# ExpressionPedalAdapter.net
KiCad netlist of a schematic drawn in EAGLE
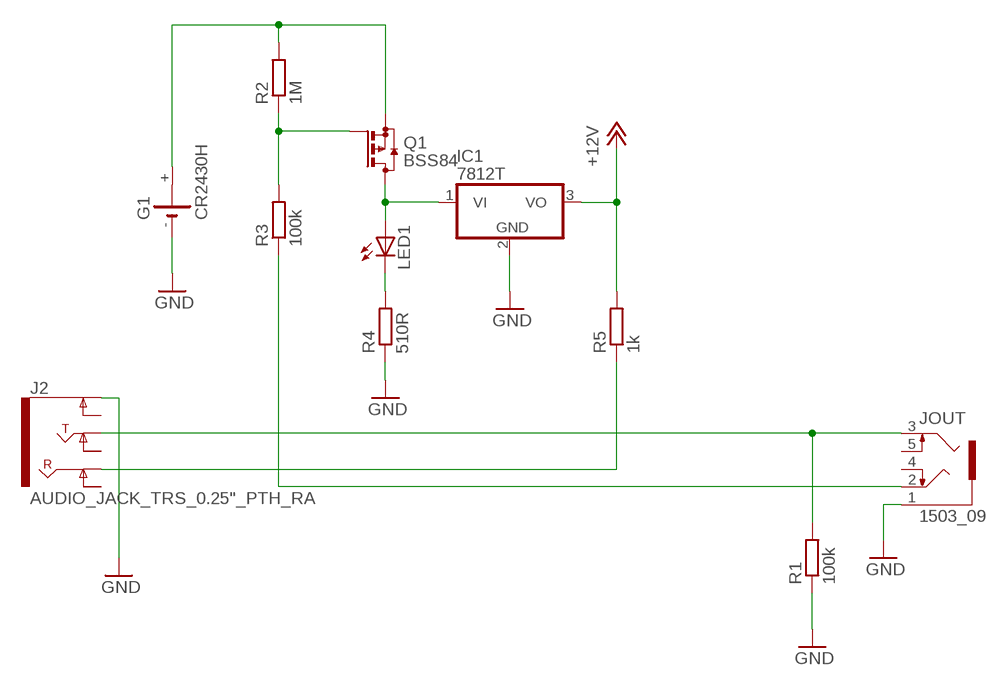
[diagram p0: schematic, sheet 1]

(export (version "E")
  (design (tool "Eeschema 10.0.6"))
  (components
    (comp (ref "G1")
      (value "CR2430H")
      (footprint "eagle-import:CR2430H")
      (libsource (lib "eagle-import") (part "CR2430H"))
    )
    (comp (ref "IC1")
      (value "7812T")
      (footprint "eagle-import:TO220H")
      (libsource (lib "eagle-import") (part "78T12"))
    )
    (comp (ref "J2")
      (value "AUDIO_JACK_TRS_0.25\"_PTH_RA")
      (footprint "eagle-import:AUDIO_JACK_0.25__TRS_PTH_RA")
      (libsource (lib "eagle-import") (part "AUDIO_JACK_TRS_0.25{dblquote}_PTH_RA"))
    )
    (comp (ref "JOUT")
      (value "1503_09")
      (footprint "eagle-import:1503_09")
      (libsource (lib "eagle-import") (part "1503_09"))
    )
    (comp (ref "LED1")
      (value "LED3MM")
      (footprint "eagle-import:LED3MM")
      (libsource (lib "eagle-import") (part "LED3MM"))
    )
    (comp (ref "Q1")
      (value "BSS84")
      (footprint "eagle-import:SOT23")
      (libsource (lib "eagle-import") (part "BSS84"))
    )
    (comp (ref "R1")
      (value "100k")
      (footprint "eagle-import:0204_7")
      (libsource (lib "eagle-import") (part "R-EU_0204/7"))
    )
    (comp (ref "R2")
      (value "1M")
      (footprint "eagle-import:0204_7")
      (libsource (lib "eagle-import") (part "R-EU_0204/7"))
    )
    (comp (ref "R3")
      (value "100k")
      (footprint "eagle-import:0204_7")
      (libsource (lib "eagle-import") (part "R-EU_0204/7"))
    )
    (comp (ref "R4")
      (value "510R")
      (footprint "eagle-import:0204_7")
      (libsource (lib "eagle-import") (part "R-EU_0204/7"))
    )
    (comp (ref "R5")
      (value "1k")
      (footprint "eagle-import:0204_7")
      (libsource (lib "eagle-import") (part "R-EU_0204/7"))
    )
  )
  (nets
    (net (code "1") (name "+12V") (class "Default")
      (node (ref "IC1") (pin "3") (pinfunction "VO_3") (pintype "passive"))
      (node (ref "R5") (pin "2") (pinfunction "2_2") (pintype "passive"))
    )
    (net (code "2") (name "GND") (class "Default")
      (node (ref "G1") (pin "-") (pinfunction "-_-") (pintype "passive"))
      (node (ref "IC1") (pin "2") (pinfunction "GND_2") (pintype "passive"))
      (node (ref "J2") (pin "SLEEVE") (pinfunction "EARTH_SLEEVE") (pintype "bidirectional"))
      (node (ref "JOUT") (pin "1") (pinfunction "1_1") (pintype "passive"))
      (node (ref "R1") (pin "1") (pinfunction "1_1") (pintype "passive"))
      (node (ref "R4") (pin "1") (pinfunction "1_1") (pintype "passive"))
    )
    (net (code "3") (name "Net-(IC1-VI)") (class "Default")
      (node (ref "IC1") (pin "1") (pinfunction "VI_1") (pintype "input"))
      (node (ref "LED1") (pin "A") (pinfunction "A_A") (pintype "passive"))
      (node (ref "Q1") (pin "3") (pinfunction "D_3") (pintype "passive"))
    )
    (net (code "4") (name "Net-(J2-PadRING)") (class "Default")
      (node (ref "J2") (pin "RING") (pinfunction "RING_RING") (pintype "bidirectional"))
      (node (ref "R5") (pin "1") (pinfunction "1_1") (pintype "passive"))
    )
    (net (code "5") (name "Net-(J2-PadTIP)") (class "Default")
      (node (ref "J2") (pin "TIP") (pinfunction "TIP_TIP") (pintype "bidirectional"))
      (node (ref "JOUT") (pin "3") (pinfunction "3_3") (pintype "passive"))
      (node (ref "R1") (pin "2") (pinfunction "2_2") (pintype "passive"))
    )
    (net (code "6") (name "Net-(JOUT-Pad2)") (class "Default")
      (node (ref "JOUT") (pin "2") (pinfunction "2_2") (pintype "passive"))
      (node (ref "R3") (pin "1") (pinfunction "1_1") (pintype "passive"))
    )
    (net (code "7") (name "Net-(LED1-C)") (class "Default")
      (node (ref "LED1") (pin "K") (pinfunction "C_K") (pintype "passive"))
      (node (ref "R4") (pin "2") (pinfunction "2_2") (pintype "passive"))
    )
    (net (code "8") (name "Net-(Q1-G)") (class "Default")
      (node (ref "Q1") (pin "1") (pinfunction "G_1") (pintype "passive"))
      (node (ref "R2") (pin "1") (pinfunction "1_1") (pintype "passive"))
      (node (ref "R3") (pin "2") (pinfunction "2_2") (pintype "passive"))
    )
    (net (code "9") (name "Net-(Q1-S)") (class "Default")
      (node (ref "G1") (pin "+") (pinfunction "+_+") (pintype "passive"))
      (node (ref "Q1") (pin "2") (pinfunction "S_2") (pintype "passive"))
      (node (ref "R2") (pin "2") (pinfunction "2_2") (pintype "passive"))
    )
    (net (code "10") (name "unconnected-(G1-+-Pad+@1)") (class "Default")
      (node (ref "G1") (pin "+@1") (pinfunction "+_+@1") (pintype "passive"))
    )
    (net (code "11") (name "unconnected-(J2-EARTH-NORM-PadSLEEVE-NORM)") (class "Default")
      (node (ref "J2") (pin "SLEEVE-NORM") (pinfunction "EARTH-NORM_SLEEVE-NORM") (pintype "bidirectional"))
    )
    (net (code "12") (name "unconnected-(J2-PadRING-NORM)") (class "Default")
      (node (ref "J2") (pin "RING-NORM") (pinfunction "RING-NORM_RING-NORM") (pintype "bidirectional"))
    )
    (net (code "13") (name "unconnected-(J2-PadTIP-NORM)") (class "Default")
      (node (ref "J2") (pin "TIP-NORM") (pinfunction "TIP-NORM_TIP-NORM") (pintype "bidirectional"))
    )
    (net (code "14") (name "unconnected-(JOUT-Pad4)") (class "Default")
      (node (ref "JOUT") (pin "4") (pinfunction "4_4") (pintype "passive"))
    )
    (net (code "15") (name "unconnected-(JOUT-Pad5)") (class "Default")
      (node (ref "JOUT") (pin "5") (pinfunction "5_5") (pintype "passive"))
    )
  )
)
